# Nicla_BME688_ANNA_schematic.net
KiCad netlist of a schematic drawn in Altium Designer
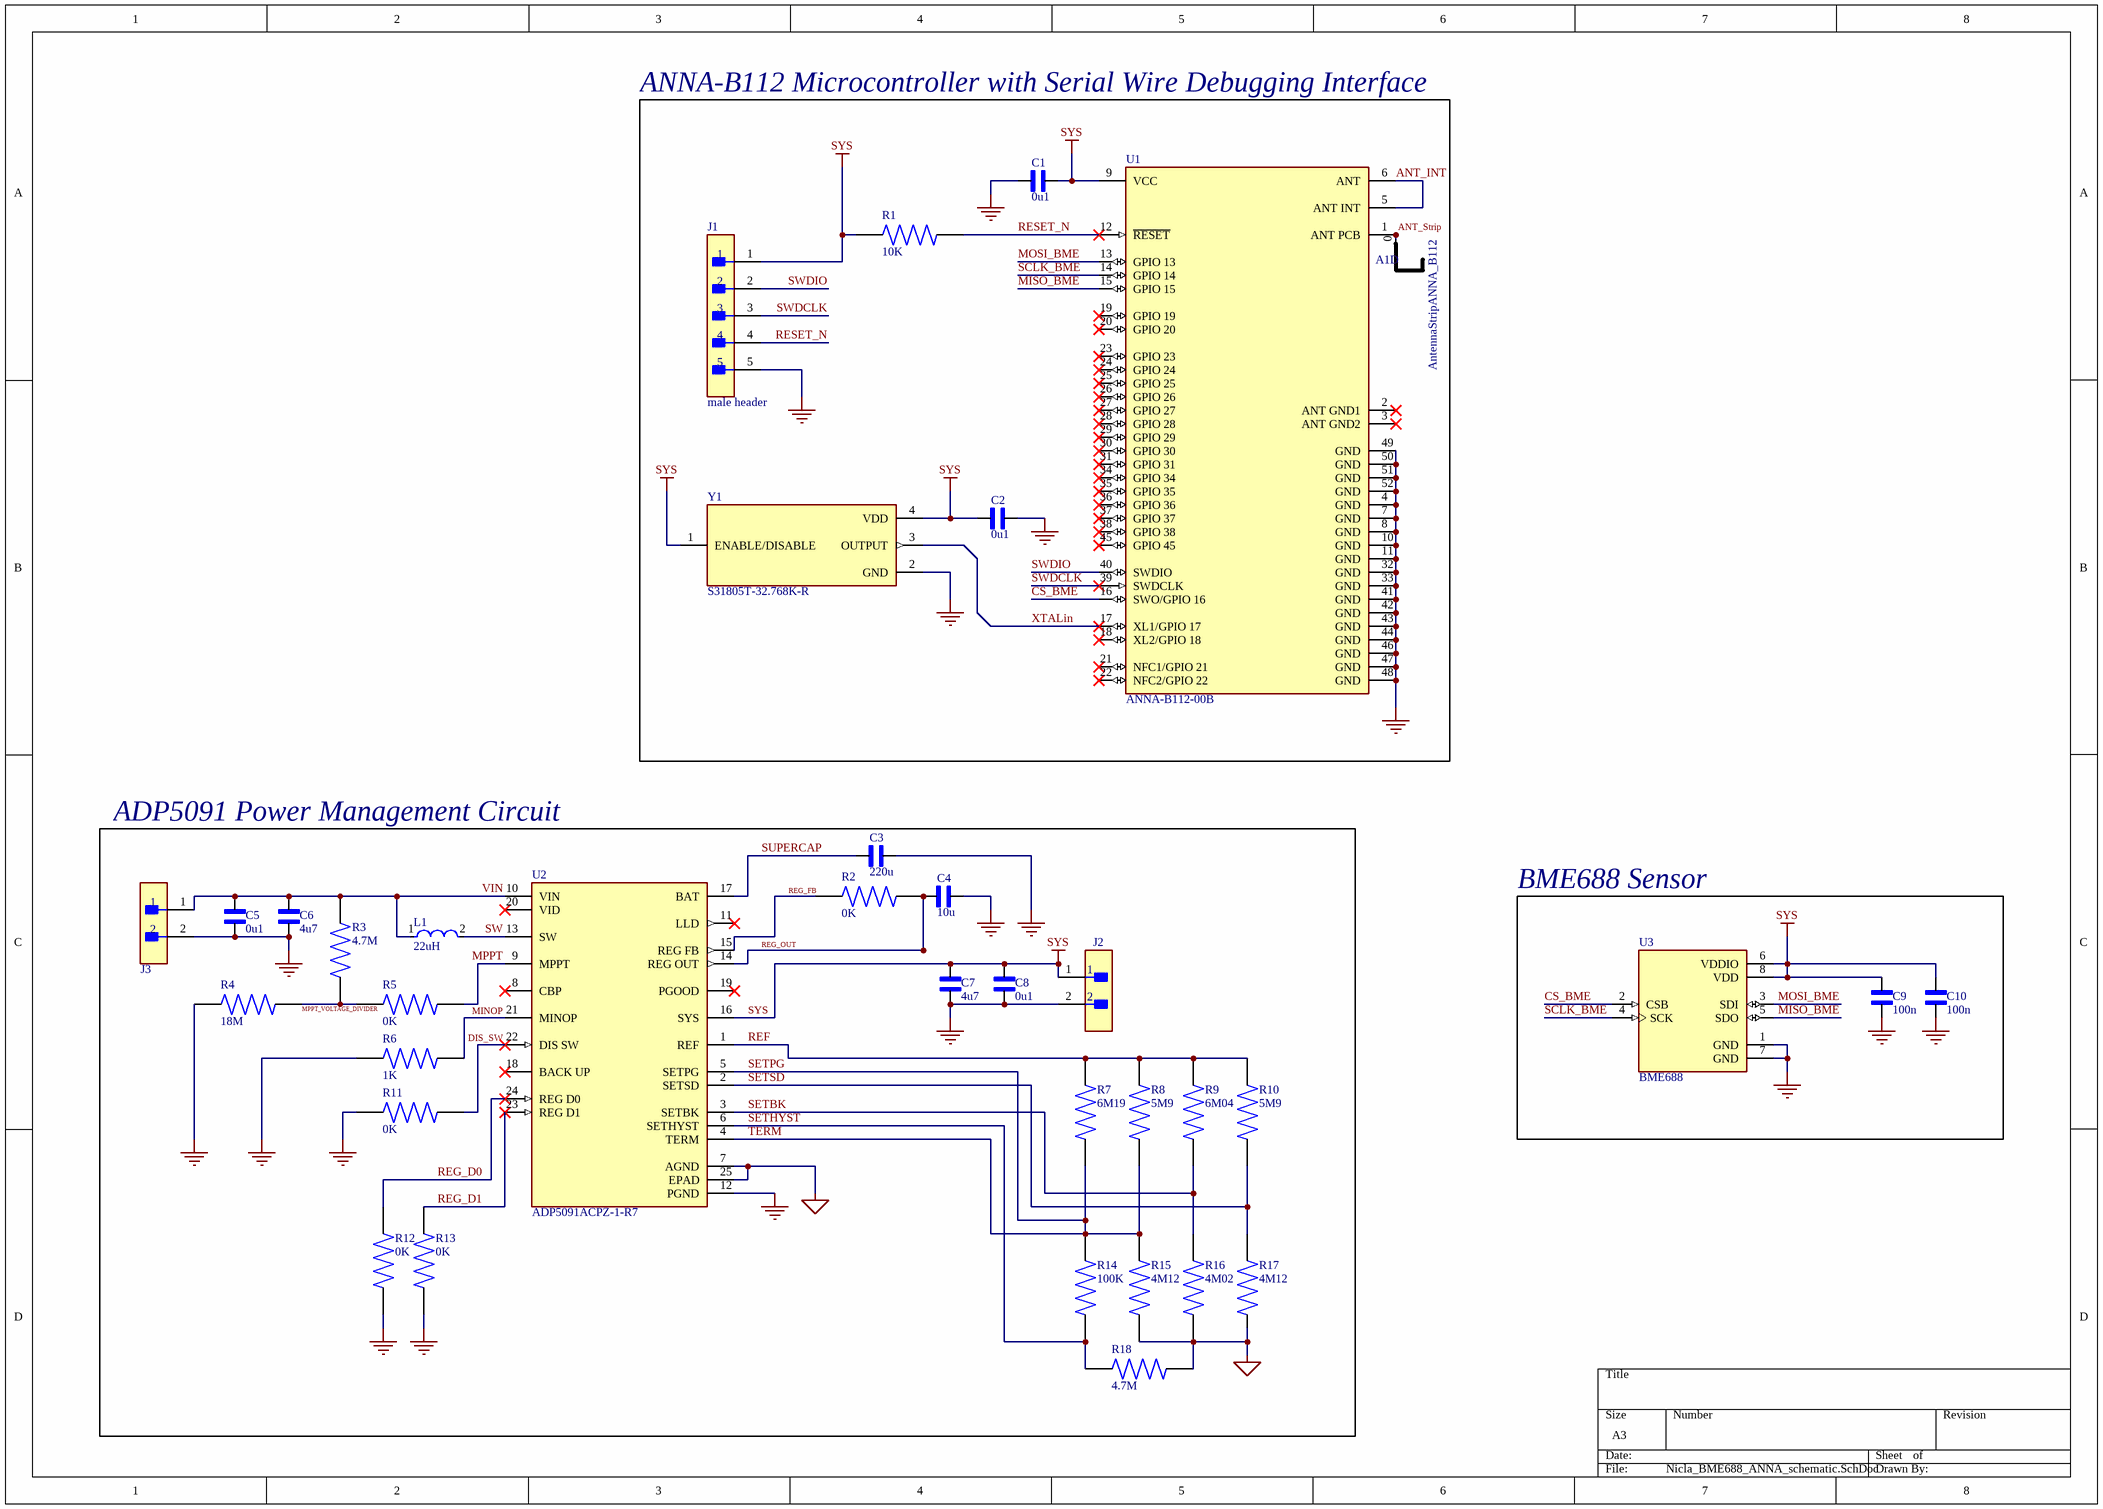
[diagram p0: Nicla_BME688_ANNA_schematic.SchDoc]

(export (version "E")
  (design (tool "Eeschema 10.0.6"))
  (components
    (comp (ref "A1")
      (value "AntennaStripANNA_B112")
      (footprint "ChipAntennaANNAB112")
      (description "Schematic for Antenna Strip for ANNA-B112 INTERNAL Antenna when chip is mounted on corner")
      (libsource (lib "AntennaStripSymbol") (part "AntennaStripANNA_B112"))
    )
    (comp (ref "C1")
      (value "0u1")
      (footprint "CAPC1608X90")
      (description "0603")
      (fields (field (name "MF") "Yageo") (field (name "MP") "CC0603KRX7R9BB151"))
      (libsource (lib "") (part "CC0603KRX7R9BB151_2"))
    )
    (comp (ref "C2")
      (value "0u1")
      (footprint "CAPC1608X90")
      (description "0603")
      (fields (field (name "MF") "Yageo") (field (name "MP") "CC0603KRX7R9BB151"))
      (libsource (lib "CC0603KRX7R9BB151") (part "CC0603KRX7R9BB151"))
    )
    (comp (ref "C3")
      (value "220u")
      (footprint "CAPC3325X152N")
      (description "1210")
      (fields (field (name "MF") "Yageo") (field (name "MP") "CC0603KRX7R9BB151"))
      (libsource (lib "") (part "CC0603KRX7R9BB151_1"))
    )
    (comp (ref "C4")
      (value "10u")
      (footprint "CAPC1608X90")
      (description "0603")
      (fields (field (name "MF") "Yageo") (field (name "MP") "CC0603KRX7R9BB151"))
      (libsource (lib "CC0603KRX7R9BB151") (part "CC0603KRX7R9BB151"))
    )
    (comp (ref "C5")
      (value "0u1")
      (footprint "CAPC1608X90")
      (description "0603")
      (fields (field (name "MF") "Yageo") (field (name "MP") "CC0603KRX7R9BB151"))
      (libsource (lib "CC0603KRX7R9BB151") (part "CC0603KRX7R9BB151"))
    )
    (comp (ref "C6")
      (value "4u7")
      (footprint "CAPC1608X90")
      (description "0603")
      (fields (field (name "MF") "Yageo") (field (name "MP") "CC0603KRX7R9BB151"))
      (libsource (lib "CC0603KRX7R9BB151") (part "CC0603KRX7R9BB151"))
    )
    (comp (ref "C7")
      (value "4u7")
      (footprint "CAPC1608X90")
      (description "0603")
      (fields (field (name "MF") "Yageo") (field (name "MP") "CC0603KRX7R9BB151"))
      (libsource (lib "") (part "CC0603KRX7R9BB151_3"))
    )
    (comp (ref "C8")
      (value "0u1")
      (footprint "CAPC1608X90")
      (description "0603")
      (fields (field (name "MF") "Yageo") (field (name "MP") "CC0603KRX7R9BB151"))
      (libsource (lib "") (part "CC0603KRX7R9BB151_3"))
    )
    (comp (ref "C9")
      (value "100n")
      (footprint "CAPC0603X33N")
      (description "0201")
      (fields (field (name "MF") "Yageo") (field (name "MP") "CC0603KRX7R9BB151"))
      (libsource (lib "") (part "CC0603KRX7R9BB151_2"))
    )
    (comp (ref "C10")
      (value "100n")
      (footprint "CAPC0603X33N")
      (description "0201")
      (fields (field (name "MF") "Yageo") (field (name "MP") "CC0603KRX7R9BB151"))
      (libsource (lib "") (part "CC0603KRX7R9BB151_2"))
    )
    (comp (ref "J1")
      (value "male header")
      (footprint "FP-22-28-4050-MFG")
      (description "CONN HEADER VERT 5Pin 2.54MM")
      (libsource (lib "Altium Content Vault") (part "bf93c07fd2649a848d0ec8585582aab"))
    )
    (comp (ref "J2")
      (value "male header")
      (footprint "FP-TSW-102-12-T-S-MFG")
      (description "CONN HEADER VERT 2POS 2.54MM")
      (libsource (lib "") (part "3bc925449376181038e59eaffc5286c_1"))
    )
    (comp (ref "J3")
      (value "male header")
      (footprint "FP-TSW-102-12-T-S-MFG")
      (description "CONN HEADER VERT 2POS 2.54MM")
      (libsource (lib "Altium Content Vault") (part "3bc925449376181038e59eaffc5286c"))
    )
    (comp (ref "L1")
      (value "22uH")
      (footprint "FP-LQH3NPH_ME-MFG")
      (description "1212")
      (fields (field (name "TOLERANCE") "20%"))
      (libsource (lib "Altium Content Vault") (part "725321dda6339637d4d059423bc1c3c"))
    )
    (comp (ref "R1")
      (value "10K")
      (footprint "RES_ERJU03J682V")
      (description "0402")
      (fields (field (name "MP") "ERJU02J364X"))
      (libsource (lib "ERJU02J364X") (part "ERJU02J364X"))
    )
    (comp (ref "R2")
      (value "0K")
      (footprint "RES_ERJU03J682V")
      (description "0402")
      (fields (field (name "MP") "ERJU02J364X"))
      (libsource (lib "ERJU02J364X") (part "ERJU02J364X"))
    )
    (comp (ref "R3")
      (value "4.7M")
      (footprint "RES_ERJU03J682V")
      (description "0402")
      (fields (field (name "MP") "ERJU02J364X"))
      (libsource (lib "ERJU02J364X") (part "ERJU02J364X"))
    )
    (comp (ref "R4")
      (value "18M")
      (footprint "RES_ERJU03J682V")
      (description "0402")
      (fields (field (name "MP") "ERJU02J364X"))
      (libsource (lib "ERJU02J364X") (part "ERJU02J364X"))
    )
    (comp (ref "R5")
      (value "0K")
      (footprint "RES_ERJU03J682V")
      (description "0402")
      (fields (field (name "MP") "ERJU02J364X"))
      (libsource (lib "ERJU02J364X") (part "ERJU02J364X"))
    )
    (comp (ref "R6")
      (value "1K")
      (footprint "RES_ERJU03J682V")
      (description "0402")
      (fields (field (name "MP") "ERJU02J364X"))
      (libsource (lib "ERJU02J364X") (part "ERJU02J364X"))
    )
    (comp (ref "R7")
      (value "6M19")
      (footprint "RES_ERJU03J682V")
      (description "0402")
      (fields (field (name "MP") "ERJU02J364X"))
      (libsource (lib "ERJU02J364X") (part "ERJU02J364X"))
    )
    (comp (ref "R8")
      (value "5M9")
      (footprint "RES_ERJU03J682V")
      (description "0402")
      (fields (field (name "MP") "ERJU02J364X"))
      (libsource (lib "ERJU02J364X") (part "ERJU02J364X"))
    )
    (comp (ref "R9")
      (value "6M04")
      (footprint "RES_ERJU03J682V")
      (description "0402")
      (fields (field (name "MP") "ERJU02J364X"))
      (libsource (lib "ERJU02J364X") (part "ERJU02J364X"))
    )
    (comp (ref "R10")
      (value "5M9")
      (footprint "RES_ERJU03J682V")
      (description "0402")
      (fields (field (name "MP") "ERJU02J364X"))
      (libsource (lib "ERJU02J364X") (part "ERJU02J364X"))
    )
    (comp (ref "R11")
      (value "0K")
      (footprint "RES_ERJU03J682V")
      (description "0402")
      (fields (field (name "MP") "ERJU02J364X"))
      (libsource (lib "ERJU02J364X") (part "ERJU02J364X"))
    )
    (comp (ref "R12")
      (value "0K")
      (footprint "RES_ERJU03J682V")
      (description "0402")
      (fields (field (name "MP") "ERJU02J364X"))
      (libsource (lib "ERJU02J364X") (part "ERJU02J364X"))
    )
    (comp (ref "R13")
      (value "0K")
      (footprint "RES_ERJU03J682V")
      (description "0402")
      (fields (field (name "MP") "ERJU02J364X"))
      (libsource (lib "ERJU02J364X") (part "ERJU02J364X"))
    )
    (comp (ref "R14")
      (value "100K")
      (footprint "RES_ERJU03J682V")
      (description "0402")
      (fields (field (name "MP") "ERJU02J364X"))
      (libsource (lib "ERJU02J364X") (part "ERJU02J364X"))
    )
    (comp (ref "R15")
      (value "4M12")
      (footprint "RES_ERJU03J682V")
      (description "0402")
      (fields (field (name "MP") "ERJU02J364X"))
      (libsource (lib "ERJU02J364X") (part "ERJU02J364X"))
    )
    (comp (ref "R16")
      (value "4M02")
      (footprint "RES_ERJU03J682V")
      (description "0402")
      (fields (field (name "MP") "ERJU02J364X"))
      (libsource (lib "ERJU02J364X") (part "ERJU02J364X"))
    )
    (comp (ref "R17")
      (value "4M12")
      (footprint "RES_ERJU03J682V")
      (description "0402")
      (fields (field (name "MP") "ERJU02J364X"))
      (libsource (lib "ERJU02J364X") (part "ERJU02J364X"))
    )
    (comp (ref "R18")
      (value "4.7M")
      (footprint "RES_ERJU03J682V")
      (description "0402")
      (fields (field (name "MP") "ERJU02J364X"))
      (libsource (lib "ERJU02J364X") (part "ERJU02J364X"))
    )
    (comp (ref "U1")
      (value "ANNA-B112-00B")
      (footprint "FP-ANNA-B112-00B-0")
      (description "RF RECEIVER GFSK 2.4GHZ")
      (fields
        (field (name "OCTOPART") "https://octopart.com/anna-b112-00b-u-blox-97577862")
        (field (name "MANUFACTURER") "U-Blox")
      )
      (libsource (lib "Altium Content Vault") (part "6e6e3db2864a6b60a663140fc6d1164"))
    )
    (comp (ref "U2")
      (value "ADP5091ACPZ-1-R7")
      (footprint "FP-CP-24-14-IPC_C")
      (description "IC BATT CHG MULTI-CHEM 24LFCSP")
      (fields
        (field (name "OCTOPART") "https://octopart.com/adp5091acpz-1-r7-analog+devices-71032930")
        (field (name "MANUFACTURER") "Analog Devices Inc.")
      )
      (libsource (lib "Altium Content Vault") (part "c7ab5527c67a22a094bbf21ec2a60f2"))
    )
    (comp (ref "U3")
      (value "BME688")
      (footprint "IC_BME688")
      (description "Gas sensor measuring relative humidity, barometric pressure, ambient temperature and gas (VOC)")
      (libsource (lib "BME688") (part "BME688"))
    )
    (comp (ref "Y1")
      (value "S31805T-32.768K-R")
      (footprint "OSC_S31805T-32.768K-R")
      (description "32KHz oscillator")
      (libsource (lib "S31805T-32.768K-R(smdOsc32khz)") (part "S31805T-32.768K-R"))
    )
  )
  (nets
    (net (code "1") (name "/ANT_INT") (class "Default")
      (node (ref "U1") (pin "5") (pinfunction "ANT_INT_5") (pintype "passive"))
      (node (ref "U1") (pin "6") (pinfunction "ANT_6") (pintype "passive"))
    )
    (net (code "2") (name "/ANT_Strip") (class "Default")
      (node (ref "A1") (pin "0") (pinfunction "0_0") (pintype "passive"))
      (node (ref "U1") (pin "1") (pinfunction "ANT_PCB_1") (pintype "passive"))
    )
    (net (code "3") (name "/CS_BME") (class "Default")
      (node (ref "U1") (pin "16") (pinfunction "SWO/GPIO_16_16") (pintype "bidirectional"))
      (node (ref "U3") (pin "2") (pinfunction "CSB_2") (pintype "input"))
    )
    (net (code "4") (name "/DIS_SW") (class "Default")
      (node (ref "R11") (pin "1") (pinfunction "1_1") (pintype "passive"))
      (node (ref "U2") (pin "22") (pinfunction "DIS_SW_22") (pintype "input"))
    )
    (net (code "5") (name "/MINOP") (class "Default")
      (node (ref "R6") (pin "1") (pinfunction "1_1") (pintype "passive"))
      (node (ref "U2") (pin "21") (pinfunction "MINOP_21") (pintype "power_in"))
    )
    (net (code "6") (name "/MISO_BME") (class "Default")
      (node (ref "U1") (pin "15") (pinfunction "GPIO_15_15") (pintype "bidirectional"))
      (node (ref "U3") (pin "5") (pinfunction "SDO_5") (pintype "bidirectional"))
    )
    (net (code "7") (name "/MOSI_BME") (class "Default")
      (node (ref "U1") (pin "13") (pinfunction "GPIO_13_13") (pintype "bidirectional"))
      (node (ref "U3") (pin "3") (pinfunction "SDI_3") (pintype "bidirectional"))
    )
    (net (code "8") (name "/MPPT") (class "Default")
      (node (ref "R5") (pin "1") (pinfunction "1_1") (pintype "passive"))
      (node (ref "U2") (pin "9") (pinfunction "MPPT_9") (pintype "passive"))
    )
    (net (code "9") (name "/MPPT_VOLTAGE_DIVIDER") (class "Default")
      (node (ref "R3") (pin "2") (pinfunction "2_2") (pintype "passive"))
      (node (ref "R4") (pin "1") (pinfunction "1_1") (pintype "passive"))
      (node (ref "R5") (pin "2") (pinfunction "2_2") (pintype "passive"))
    )
    (net (code "10") (name "/REF") (class "Default")
      (node (ref "R10") (pin "1") (pinfunction "1_1") (pintype "passive"))
      (node (ref "R7") (pin "1") (pinfunction "1_1") (pintype "passive"))
      (node (ref "R8") (pin "1") (pinfunction "1_1") (pintype "passive"))
      (node (ref "R9") (pin "1") (pinfunction "1_1") (pintype "passive"))
      (node (ref "U2") (pin "1") (pinfunction "REF_1") (pintype "power_in"))
    )
    (net (code "11") (name "/REG_D0") (class "Default")
      (node (ref "R12") (pin "2") (pinfunction "2_2") (pintype "passive"))
      (node (ref "U2") (pin "24") (pinfunction "REG_D0_24") (pintype "input"))
    )
    (net (code "12") (name "/REG_D1") (class "Default")
      (node (ref "R13") (pin "2") (pinfunction "2_2") (pintype "passive"))
      (node (ref "U2") (pin "23") (pinfunction "REG_D1_23") (pintype "input"))
    )
    (net (code "13") (name "/REG_FB") (class "Default")
      (node (ref "R2") (pin "2") (pinfunction "2_2") (pintype "passive"))
      (node (ref "U2") (pin "15") (pinfunction "REG_FB_15") (pintype "output"))
    )
    (net (code "14") (name "/REG_OUT") (class "Default")
      (node (ref "C4") (pin "2") (pinfunction "2_2") (pintype "passive"))
      (node (ref "R2") (pin "1") (pinfunction "1_1") (pintype "passive"))
      (node (ref "U2") (pin "14") (pinfunction "REG_OUT_14") (pintype "output"))
    )
    (net (code "15") (name "/RESET_N") (class "Default")
      (node (ref "J1") (pin "4") (pinfunction "4_4") (pintype "passive"))
      (node (ref "R1") (pin "1") (pinfunction "1_1") (pintype "passive"))
      (node (ref "U1") (pin "12") (pinfunction "~{RESET}_12") (pintype "input"))
    )
    (net (code "16") (name "/SCLK_BME") (class "Default")
      (node (ref "U1") (pin "14") (pinfunction "GPIO_14_14") (pintype "bidirectional"))
      (node (ref "U3") (pin "4") (pinfunction "SCK_4") (pintype "input"))
    )
    (net (code "17") (name "/SETBK") (class "Default")
      (node (ref "R16") (pin "1") (pinfunction "1_1") (pintype "passive"))
      (node (ref "R9") (pin "2") (pinfunction "2_2") (pintype "passive"))
      (node (ref "U2") (pin "3") (pinfunction "SETBK_3") (pintype "passive"))
    )
    (net (code "18") (name "/SETHYST") (class "Default")
      (node (ref "R14") (pin "2") (pinfunction "2_2") (pintype "passive"))
      (node (ref "R18") (pin "1") (pinfunction "1_1") (pintype "passive"))
      (node (ref "U2") (pin "6") (pinfunction "SETHYST_6") (pintype "passive"))
    )
    (net (code "19") (name "/SETPG") (class "Default")
      (node (ref "R14") (pin "1") (pinfunction "1_1") (pintype "passive"))
      (node (ref "R15") (pin "1") (pinfunction "1_1") (pintype "passive"))
      (node (ref "R7") (pin "2") (pinfunction "2_2") (pintype "passive"))
      (node (ref "R8") (pin "2") (pinfunction "2_2") (pintype "passive"))
      (node (ref "U2") (pin "4") (pinfunction "TERM_4") (pintype "passive"))
      (node (ref "U2") (pin "5") (pinfunction "SETPG_5") (pintype "passive"))
    )
    (net (code "20") (name "/SETSD") (class "Default")
      (node (ref "R10") (pin "2") (pinfunction "2_2") (pintype "passive"))
      (node (ref "R17") (pin "1") (pinfunction "1_1") (pintype "passive"))
      (node (ref "U2") (pin "2") (pinfunction "SETSD_2") (pintype "passive"))
    )
    (net (code "21") (name "/SUPERCAP") (class "Default")
      (node (ref "C3") (pin "1") (pinfunction "1_1") (pintype "passive"))
      (node (ref "U2") (pin "17") (pinfunction "BAT_17") (pintype "power_in"))
    )
    (net (code "22") (name "/SW") (class "Default")
      (node (ref "L1") (pin "2") (pinfunction "2_2") (pintype "passive"))
      (node (ref "U2") (pin "13") (pinfunction "SW_13") (pintype "passive"))
    )
    (net (code "23") (name "/SWDCLK") (class "Default")
      (node (ref "J1") (pin "3") (pinfunction "3_3") (pintype "passive"))
      (node (ref "U1") (pin "39") (pinfunction "SWDCLK_39") (pintype "input"))
    )
    (net (code "24") (name "/SWDIO") (class "Default")
      (node (ref "J1") (pin "2") (pinfunction "2_2") (pintype "passive"))
      (node (ref "U1") (pin "40") (pinfunction "SWDIO_40") (pintype "bidirectional"))
    )
    (net (code "25") (name "/VIN") (class "Default")
      (node (ref "C5") (pin "1") (pinfunction "1_1") (pintype "passive"))
      (node (ref "C6") (pin "1") (pinfunction "1_1") (pintype "passive"))
      (node (ref "J3") (pin "1") (pinfunction "1_1") (pintype "passive"))
      (node (ref "L1") (pin "1") (pinfunction "1_1") (pintype "passive"))
      (node (ref "R3") (pin "1") (pinfunction "1_1") (pintype "passive"))
      (node (ref "U2") (pin "10") (pinfunction "VIN_10") (pintype "power_in"))
    )
    (net (code "26") (name "/XTALin") (class "Default")
      (node (ref "U1") (pin "17") (pinfunction "XL1/GPIO_17_17") (pintype "bidirectional"))
      (node (ref "Y1") (pin "3") (pinfunction "OUTPUT_3") (pintype "output"))
    )
    (net (code "27") (name "GND") (class "Default")
      (node (ref "C1") (pin "1") (pinfunction "1_1") (pintype "passive"))
      (node (ref "C10") (pin "1") (pinfunction "1_1") (pintype "passive"))
      (node (ref "C2") (pin "1") (pinfunction "1_1") (pintype "passive"))
      (node (ref "C3") (pin "2") (pinfunction "2_2") (pintype "passive"))
      (node (ref "C4") (pin "1") (pinfunction "1_1") (pintype "passive"))
      (node (ref "C5") (pin "2") (pinfunction "2_2") (pintype "passive"))
      (node (ref "C6") (pin "2") (pinfunction "2_2") (pintype "passive"))
      (node (ref "C7") (pin "2") (pinfunction "2_2") (pintype "passive"))
      (node (ref "C8") (pin "2") (pinfunction "2_2") (pintype "passive"))
      (node (ref "C9") (pin "1") (pinfunction "1_1") (pintype "passive"))
      (node (ref "J1") (pin "5") (pinfunction "5_5") (pintype "passive"))
      (node (ref "J2") (pin "2") (pinfunction "2_2") (pintype "passive"))
      (node (ref "J3") (pin "2") (pinfunction "2_2") (pintype "passive"))
      (node (ref "R11") (pin "2") (pinfunction "2_2") (pintype "passive"))
      (node (ref "R12") (pin "1") (pinfunction "1_1") (pintype "passive"))
      (node (ref "R13") (pin "1") (pinfunction "1_1") (pintype "passive"))
      (node (ref "R15") (pin "2") (pinfunction "2_2") (pintype "passive"))
      (node (ref "R16") (pin "2") (pinfunction "2_2") (pintype "passive"))
      (node (ref "R17") (pin "2") (pinfunction "2_2") (pintype "passive"))
      (node (ref "R18") (pin "2") (pinfunction "2_2") (pintype "passive"))
      (node (ref "R4") (pin "2") (pinfunction "2_2") (pintype "passive"))
      (node (ref "R6") (pin "2") (pinfunction "2_2") (pintype "passive"))
      (node (ref "U1") (pin "10") (pinfunction "GND_10") (pintype "power_in"))
      (node (ref "U1") (pin "11") (pinfunction "GND_11") (pintype "power_in"))
      (node (ref "U1") (pin "32") (pinfunction "GND_32") (pintype "power_in"))
      (node (ref "U1") (pin "33") (pinfunction "GND_33") (pintype "power_in"))
      (node (ref "U1") (pin "4") (pinfunction "GND_4") (pintype "power_in"))
      (node (ref "U1") (pin "41") (pinfunction "GND_41") (pintype "power_in"))
      (node (ref "U1") (pin "42") (pinfunction "GND_42") (pintype "power_in"))
      (node (ref "U1") (pin "43") (pinfunction "GND_43") (pintype "power_in"))
      (node (ref "U1") (pin "44") (pinfunction "GND_44") (pintype "power_in"))
      (node (ref "U1") (pin "46") (pinfunction "GND_46") (pintype "power_in"))
      (node (ref "U1") (pin "47") (pinfunction "GND_47") (pintype "power_in"))
      (node (ref "U1") (pin "48") (pinfunction "GND_48") (pintype "power_in"))
      (node (ref "U1") (pin "49") (pinfunction "GND_49") (pintype "power_in"))
      (node (ref "U1") (pin "50") (pinfunction "GND_50") (pintype "power_in"))
      (node (ref "U1") (pin "51") (pinfunction "GND_51") (pintype "power_in"))
      (node (ref "U1") (pin "52") (pinfunction "GND_52") (pintype "power_in"))
      (node (ref "U1") (pin "7") (pinfunction "GND_7") (pintype "power_in"))
      (node (ref "U1") (pin "8") (pinfunction "GND_8") (pintype "power_in"))
      (node (ref "U2") (pin "12") (pinfunction "PGND_12") (pintype "power_in"))
      (node (ref "U2") (pin "25") (pinfunction "EPAD_25") (pintype "power_in"))
      (node (ref "U2") (pin "7") (pinfunction "AGND_7") (pintype "power_in"))
      (node (ref "U3") (pin "1") (pinfunction "GND_1") (pintype "power_in"))
      (node (ref "U3") (pin "7") (pinfunction "GND_7") (pintype "power_in"))
      (node (ref "Y1") (pin "2") (pinfunction "GND_2") (pintype "power_in"))
    )
    (net (code "28") (name "SYS") (class "Default")
      (node (ref "C1") (pin "2") (pinfunction "2_2") (pintype "passive"))
      (node (ref "C10") (pin "2") (pinfunction "2_2") (pintype "passive"))
      (node (ref "C2") (pin "2") (pinfunction "2_2") (pintype "passive"))
      (node (ref "C7") (pin "1") (pinfunction "1_1") (pintype "passive"))
      (node (ref "C8") (pin "1") (pinfunction "1_1") (pintype "passive"))
      (node (ref "C9") (pin "2") (pinfunction "2_2") (pintype "passive"))
      (node (ref "J1") (pin "1") (pinfunction "1_1") (pintype "passive"))
      (node (ref "J2") (pin "1") (pinfunction "1_1") (pintype "passive"))
      (node (ref "R1") (pin "2") (pinfunction "2_2") (pintype "passive"))
      (node (ref "U1") (pin "9") (pinfunction "VCC_9") (pintype "power_in"))
      (node (ref "U2") (pin "16") (pinfunction "SYS_16") (pintype "power_in"))
      (node (ref "U3") (pin "6") (pinfunction "VDDIO_6") (pintype "power_in"))
      (node (ref "U3") (pin "8") (pinfunction "VDD_8") (pintype "power_in"))
      (node (ref "Y1") (pin "1") (pinfunction "ENABLE/DISABLE_1") (pintype "passive"))
      (node (ref "Y1") (pin "4") (pinfunction "VDD_4") (pintype "power_in"))
    )
    (net (code "29") (name "unconnected-(U1-ANT_GND1-Pad2)") (class "Default")
      (node (ref "U1") (pin "2") (pinfunction "ANT_GND1_2") (pintype "power_in+no_connect"))
    )
    (net (code "30") (name "unconnected-(U1-ANT_GND2-Pad3)") (class "Default")
      (node (ref "U1") (pin "3") (pinfunction "ANT_GND2_3") (pintype "power_in+no_connect"))
    )
    (net (code "31") (name "unconnected-(U1-GPIO_19-Pad19)") (class "Default")
      (node (ref "U1") (pin "19") (pinfunction "GPIO_19_19") (pintype "bidirectional+no_connect"))
    )
    (net (code "32") (name "unconnected-(U1-GPIO_20-Pad20)") (class "Default")
      (node (ref "U1") (pin "20") (pinfunction "GPIO_20_20") (pintype "bidirectional+no_connect"))
    )
    (net (code "33") (name "unconnected-(U1-GPIO_23-Pad23)") (class "Default")
      (node (ref "U1") (pin "23") (pinfunction "GPIO_23_23") (pintype "bidirectional+no_connect"))
    )
    (net (code "34") (name "unconnected-(U1-GPIO_24-Pad24)") (class "Default")
      (node (ref "U1") (pin "24") (pinfunction "GPIO_24_24") (pintype "bidirectional+no_connect"))
    )
    (net (code "35") (name "unconnected-(U1-GPIO_25-Pad25)") (class "Default")
      (node (ref "U1") (pin "25") (pinfunction "GPIO_25_25") (pintype "bidirectional+no_connect"))
    )
    (net (code "36") (name "unconnected-(U1-GPIO_26-Pad26)") (class "Default")
      (node (ref "U1") (pin "26") (pinfunction "GPIO_26_26") (pintype "bidirectional+no_connect"))
    )
    (net (code "37") (name "unconnected-(U1-GPIO_27-Pad27)") (class "Default")
      (node (ref "U1") (pin "27") (pinfunction "GPIO_27_27") (pintype "bidirectional+no_connect"))
    )
    (net (code "38") (name "unconnected-(U1-GPIO_28-Pad28)") (class "Default")
      (node (ref "U1") (pin "28") (pinfunction "GPIO_28_28") (pintype "bidirectional+no_connect"))
    )
    (net (code "39") (name "unconnected-(U1-GPIO_29-Pad29)") (class "Default")
      (node (ref "U1") (pin "29") (pinfunction "GPIO_29_29") (pintype "bidirectional+no_connect"))
    )
    (net (code "40") (name "unconnected-(U1-GPIO_30-Pad30)") (class "Default")
      (node (ref "U1") (pin "30") (pinfunction "GPIO_30_30") (pintype "bidirectional+no_connect"))
    )
    (net (code "41") (name "unconnected-(U1-GPIO_31-Pad31)") (class "Default")
      (node (ref "U1") (pin "31") (pinfunction "GPIO_31_31") (pintype "bidirectional+no_connect"))
    )
    (net (code "42") (name "unconnected-(U1-GPIO_34-Pad34)") (class "Default")
      (node (ref "U1") (pin "34") (pinfunction "GPIO_34_34") (pintype "bidirectional+no_connect"))
    )
    (net (code "43") (name "unconnected-(U1-GPIO_35-Pad35)") (class "Default")
      (node (ref "U1") (pin "35") (pinfunction "GPIO_35_35") (pintype "bidirectional+no_connect"))
    )
    (net (code "44") (name "unconnected-(U1-GPIO_36-Pad36)") (class "Default")
      (node (ref "U1") (pin "36") (pinfunction "GPIO_36_36") (pintype "bidirectional+no_connect"))
    )
    (net (code "45") (name "unconnected-(U1-GPIO_37-Pad37)") (class "Default")
      (node (ref "U1") (pin "37") (pinfunction "GPIO_37_37") (pintype "bidirectional+no_connect"))
    )
    (net (code "46") (name "unconnected-(U1-GPIO_38-Pad38)") (class "Default")
      (node (ref "U1") (pin "38") (pinfunction "GPIO_38_38") (pintype "bidirectional+no_connect"))
    )
    (net (code "47") (name "unconnected-(U1-GPIO_45-Pad45)") (class "Default")
      (node (ref "U1") (pin "45") (pinfunction "GPIO_45_45") (pintype "bidirectional+no_connect"))
    )
    (net (code "48") (name "unconnected-(U1-NFC1{slash}GPIO_21-Pad21)") (class "Default")
      (node (ref "U1") (pin "21") (pinfunction "NFC1/GPIO_21_21") (pintype "bidirectional+no_connect"))
    )
    (net (code "49") (name "unconnected-(U1-NFC2{slash}GPIO_22-Pad22)") (class "Default")
      (node (ref "U1") (pin "22") (pinfunction "NFC2/GPIO_22_22") (pintype "bidirectional+no_connect"))
    )
    (net (code "50") (name "unconnected-(U1-XL2{slash}GPIO_18-Pad18)") (class "Default")
      (node (ref "U1") (pin "18") (pinfunction "XL2/GPIO_18_18") (pintype "bidirectional+no_connect"))
    )
    (net (code "51") (name "unconnected-(U2-BACK_UP-Pad18)") (class "Default")
      (node (ref "U2") (pin "18") (pinfunction "BACK_UP_18") (pintype "power_in+no_connect"))
    )
    (net (code "52") (name "unconnected-(U2-CBP-Pad8)") (class "Default")
      (node (ref "U2") (pin "8") (pinfunction "CBP_8") (pintype "passive+no_connect"))
    )
    (net (code "53") (name "unconnected-(U2-LLD-Pad11)") (class "Default")
      (node (ref "U2") (pin "11") (pinfunction "LLD_11") (pintype "output+no_connect"))
    )
    (net (code "54") (name "unconnected-(U2-PGOOD-Pad19)") (class "Default")
      (node (ref "U2") (pin "19") (pinfunction "PGOOD_19") (pintype "power_in+no_connect"))
    )
    (net (code "55") (name "unconnected-(U2-VID-Pad20)") (class "Default")
      (node (ref "U2") (pin "20") (pinfunction "VID_20") (pintype "power_in+no_connect"))
    )
  )
)
